# tritiled_v30_lux_c.net
KiCad netlist of a schematic drawn in EAGLE
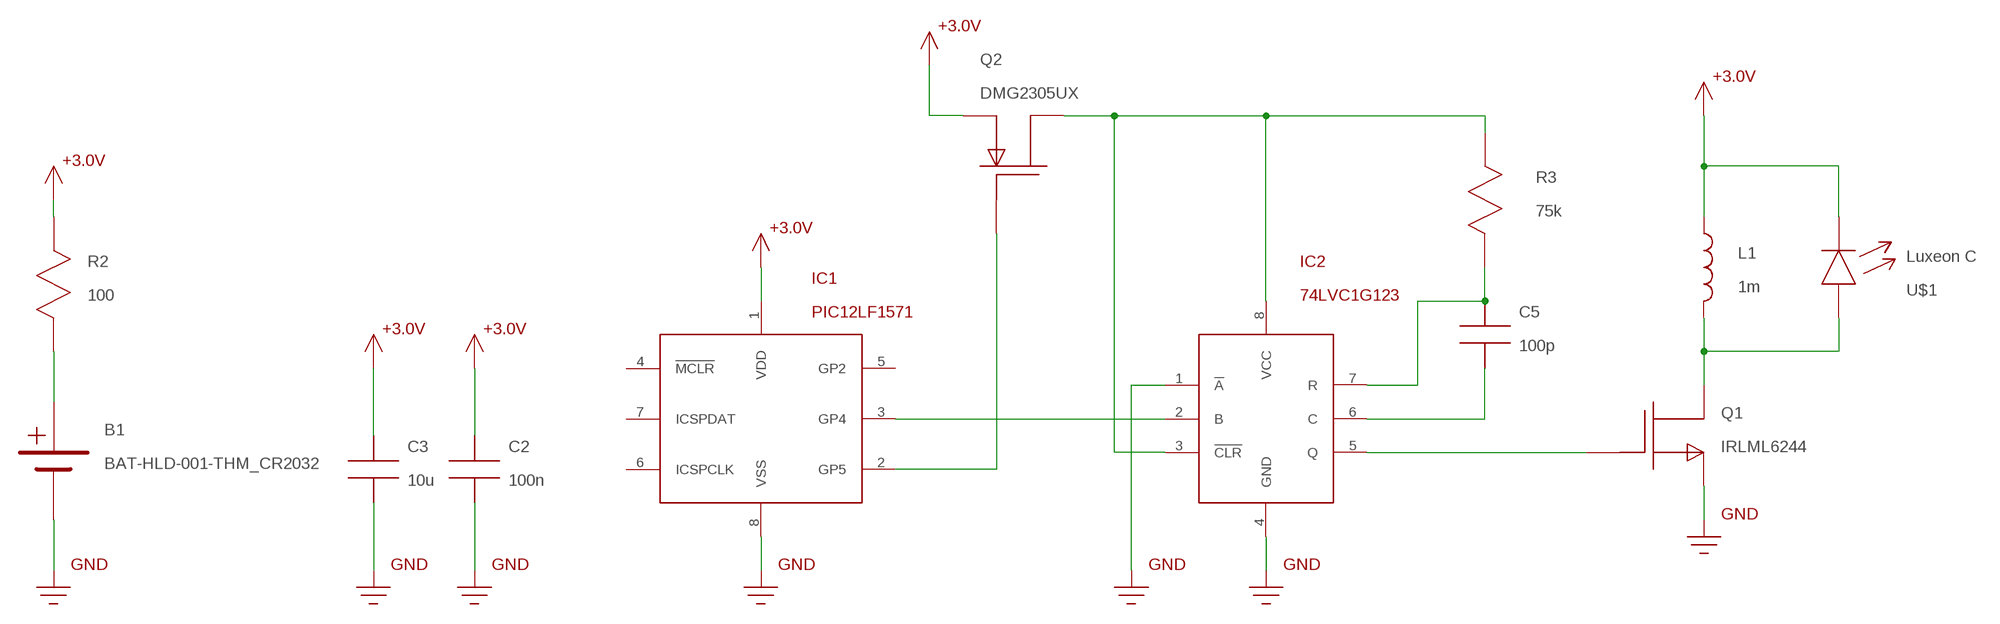
[diagram p0: schematic, sheet 1]

(export (version "E")
  (design (tool "Eeschema 10.0.6"))
  (components
    (comp (ref "B1")
      (value "BAT-HLD-001-THM_CR2032")
      (footprint "eagle-import:CR2032_BAT-HLD-001-THM")
      (libsource (lib "eagle-import") (part "BAT-HLD-001-THM_CR2032"))
    )
    (comp (ref "C2")
      (value "100n")
      (footprint "eagle-import:0805")
      (libsource (lib "eagle-import") (part "C0805"))
    )
    (comp (ref "C3")
      (value "10u")
      (footprint "eagle-import:1206")
      (libsource (lib "eagle-import") (part "C1206"))
    )
    (comp (ref "C5")
      (value "100p")
      (footprint "eagle-import:C0603")
      (libsource (lib "eagle-import") (part "C0603"))
    )
    (comp (ref "IC1")
      (value "PIC12LF1571")
      (footprint "eagle-import:SOIC8")
      (libsource (lib "eagle-import") (part "PIC12LF1571"))
    )
    (comp (ref "IC2")
      (value "74LVC1G123")
      (footprint "eagle-import:SM8")
      (libsource (lib "eagle-import") (part "74LVC1G123"))
    )
    (comp (ref "L1")
      (value "1m")
      (footprint "eagle-import:SRR6028_INDUCTOR")
      (libsource (lib "eagle-import") (part "SRR6028_INDUCTOR"))
    )
    (comp (ref "Q1")
      (value "IRLML6244")
      (footprint "eagle-import:SOT-23")
      (libsource (lib "eagle-import") (part "ZXMN3B01FSOT23"))
    )
    (comp (ref "Q2")
      (value "DMG2305UX")
      (footprint "eagle-import:SOT-23")
      (libsource (lib "eagle-import") (part "DMG2305UXSOT23"))
    )
    (comp (ref "R2")
      (value "100")
      (footprint "eagle-import:R1206")
      (libsource (lib "eagle-import") (part "R1206"))
    )
    (comp (ref "R3")
      (value "75k")
      (footprint "eagle-import:R0603")
      (libsource (lib "eagle-import") (part "R0603"))
    )
    (comp (ref "U$1")
      (value "Luxeon C")
      (footprint "eagle-import:LUXEON_C")
      (libsource (lib "eagle-import") (part "LEDLUXEON_C"))
    )
  )
  (nets
    (net (code "1") (name "+3.0V") (class "Default")
      (node (ref "C2") (pin "P$1") (pinfunction "P$1_P$1") (pintype "bidirectional"))
      (node (ref "C3") (pin "P$1") (pinfunction "P$1_P$1") (pintype "bidirectional"))
      (node (ref "IC1") (pin "1") (pinfunction "VDD_1") (pintype "bidirectional"))
      (node (ref "L1") (pin "P$1") (pinfunction "1_P$1") (pintype "passive"))
      (node (ref "Q2") (pin "2") (pinfunction "S_2") (pintype "bidirectional"))
      (node (ref "R2") (pin "P$1") (pinfunction "P$1_P$1") (pintype "bidirectional"))
      (node (ref "U$1") (pin "C") (pinfunction "C_C") (pintype "bidirectional"))
    )
    (net (code "2") (name "GND") (class "Default")
      (node (ref "B1") (pin "GND") (pinfunction "0V_GND") (pintype "power_in"))
      (node (ref "C2") (pin "P$2") (pinfunction "P$2_P$2") (pintype "bidirectional"))
      (node (ref "C3") (pin "P$2") (pinfunction "P$2_P$2") (pintype "bidirectional"))
      (node (ref "IC1") (pin "8") (pinfunction "VSS_8") (pintype "bidirectional"))
      (node (ref "IC2") (pin "1") (pinfunction "~{A}_1") (pintype "bidirectional"))
      (node (ref "IC2") (pin "4") (pinfunction "GND_4") (pintype "bidirectional"))
      (node (ref "Q1") (pin "2") (pinfunction "S_2") (pintype "bidirectional"))
    )
    (net (code "3") (name "Net-(B1-+V-Pad+V@1)") (class "Default")
      (node (ref "B1") (pin "+V@1") (pinfunction "+V_+V@1") (pintype "power_in"))
      (node (ref "B1") (pin "+V@2") (pinfunction "+V_+V@2") (pintype "power_in"))
      (node (ref "B1") (pin "+V@3") (pinfunction "+V_+V@3") (pintype "power_in"))
      (node (ref "B1") (pin "+V@4") (pinfunction "+V_+V@4") (pintype "power_in"))
      (node (ref "R2") (pin "P$2") (pinfunction "P$2_P$2") (pintype "bidirectional"))
    )
    (net (code "4") (name "Net-(IC1-GP4)") (class "Default")
      (node (ref "IC1") (pin "3") (pinfunction "GP4_3") (pintype "bidirectional"))
      (node (ref "IC2") (pin "2") (pinfunction "B_2") (pintype "bidirectional"))
    )
    (net (code "5") (name "Net-(IC1-GP5)") (class "Default")
      (node (ref "IC1") (pin "2") (pinfunction "GP5_2") (pintype "bidirectional"))
      (node (ref "Q2") (pin "1") (pinfunction "G_1") (pintype "bidirectional"))
    )
    (net (code "6") (name "Net-(IC2-C)") (class "Default")
      (node (ref "C5") (pin "P$2") (pinfunction "P$2_P$2") (pintype "bidirectional"))
      (node (ref "IC2") (pin "6") (pinfunction "C_6") (pintype "bidirectional"))
    )
    (net (code "7") (name "Net-(IC2-Q)") (class "Default")
      (node (ref "IC2") (pin "5") (pinfunction "Q_5") (pintype "bidirectional"))
      (node (ref "Q1") (pin "1") (pinfunction "G_1") (pintype "bidirectional"))
    )
    (net (code "8") (name "Net-(IC2-R)") (class "Default")
      (node (ref "C5") (pin "P$1") (pinfunction "P$1_P$1") (pintype "bidirectional"))
      (node (ref "IC2") (pin "7") (pinfunction "R_7") (pintype "bidirectional"))
      (node (ref "R3") (pin "P$1") (pinfunction "P$1_P$1") (pintype "bidirectional"))
    )
    (net (code "9") (name "Net-(IC2-VCC)") (class "Default")
      (node (ref "IC2") (pin "3") (pinfunction "~{CLR}_3") (pintype "bidirectional"))
      (node (ref "IC2") (pin "8") (pinfunction "VCC_8") (pintype "bidirectional"))
      (node (ref "Q2") (pin "3") (pinfunction "D_3") (pintype "bidirectional"))
      (node (ref "R3") (pin "P$2") (pinfunction "P$2_P$2") (pintype "bidirectional"))
    )
    (net (code "10") (name "Net-(L1-2)") (class "Default")
      (node (ref "L1") (pin "P$2") (pinfunction "2_P$2") (pintype "passive"))
      (node (ref "Q1") (pin "3") (pinfunction "D_3") (pintype "bidirectional"))
      (node (ref "U$1") (pin "A") (pinfunction "A_A") (pintype "bidirectional"))
    )
    (net (code "11") (name "unconnected-(IC1-GP2-Pad5)") (class "Default")
      (node (ref "IC1") (pin "5") (pinfunction "GP2_5") (pintype "bidirectional"))
    )
    (net (code "12") (name "unconnected-(IC1-ICSPCLK-Pad6)") (class "Default")
      (node (ref "IC1") (pin "6") (pinfunction "ICSPCLK_6") (pintype "bidirectional"))
    )
    (net (code "13") (name "unconnected-(IC1-ICSPDAT-Pad7)") (class "Default")
      (node (ref "IC1") (pin "7") (pinfunction "ICSPDAT_7") (pintype "bidirectional"))
    )
    (net (code "14") (name "unconnected-(IC1-~{MCLR}-Pad4)") (class "Default")
      (node (ref "IC1") (pin "4") (pinfunction "~{MCLR}_4") (pintype "bidirectional"))
    )
  )
)
